# Instruction_Register.net
KiCad netlist of a schematic drawn in Altium Designer
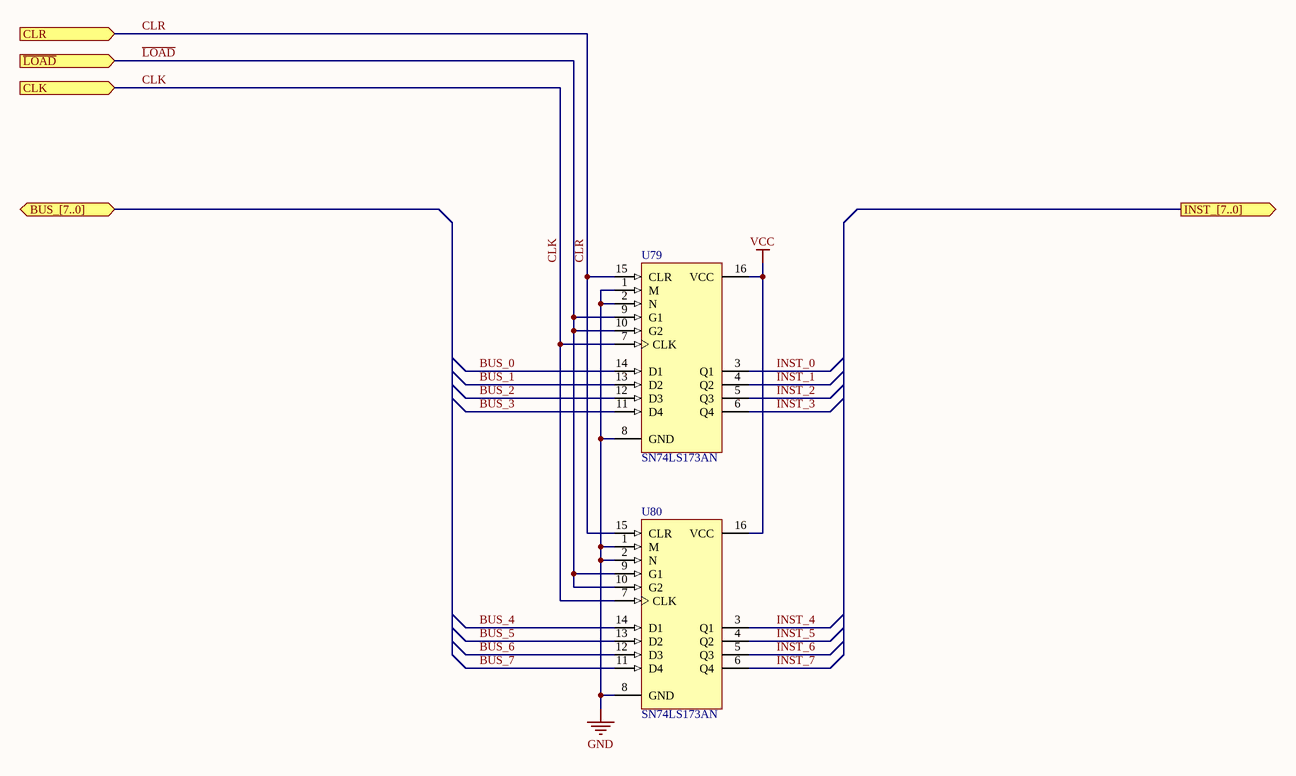
[diagram p0: Instruction Register.SchDoc]

(export (version "E")
  (design (tool "Eeschema 10.0.6"))
  (components
    (comp (ref "U79")
      (value "SN74LS173AN")
      (footprint "N016D")
      (description "4-Bit D-Type Register with 3-State Outputs")
      (fields (field (name "PUBLISHER") "Altium Limited"))
      (libsource (lib "TI Logic Flip-Flop") (part "SN74LS173AN"))
    )
    (comp (ref "U80")
      (value "SN74LS173AN")
      (footprint "N016D")
      (description "4-Bit D-Type Register with 3-State Outputs")
      (fields (field (name "PUBLISHER") "Altium Limited"))
      (libsource (lib "TI Logic Flip-Flop") (part "SN74LS173AN"))
    )
  )
  (nets
    (net (code "1") (name "/BUS_0") (class "Default")
      (node (ref "U79") (pin "14") (pinfunction "D1_14") (pintype "input"))
    )
    (net (code "2") (name "/BUS_1") (class "Default")
      (node (ref "U79") (pin "13") (pinfunction "D2_13") (pintype "input"))
    )
    (net (code "3") (name "/BUS_2") (class "Default")
      (node (ref "U79") (pin "12") (pinfunction "D3_12") (pintype "input"))
    )
    (net (code "4") (name "/BUS_3") (class "Default")
      (node (ref "U79") (pin "11") (pinfunction "D4_11") (pintype "input"))
    )
    (net (code "5") (name "/BUS_4") (class "Default")
      (node (ref "U80") (pin "14") (pinfunction "D1_14") (pintype "input"))
    )
    (net (code "6") (name "/BUS_5") (class "Default")
      (node (ref "U80") (pin "13") (pinfunction "D2_13") (pintype "input"))
    )
    (net (code "7") (name "/BUS_6") (class "Default")
      (node (ref "U80") (pin "12") (pinfunction "D3_12") (pintype "input"))
    )
    (net (code "8") (name "/BUS_7") (class "Default")
      (node (ref "U80") (pin "11") (pinfunction "D4_11") (pintype "input"))
    )
    (net (code "10") (name "/CLK") (class "Default")
      (node (ref "U79") (pin "7") (pinfunction "CLK_7") (pintype "input"))
      (node (ref "U80") (pin "7") (pinfunction "CLK_7") (pintype "input"))
    )
    (net (code "11") (name "/CLR") (class "Default")
      (node (ref "U79") (pin "15") (pinfunction "CLR_15") (pintype "input"))
      (node (ref "U80") (pin "15") (pinfunction "CLR_15") (pintype "input"))
    )
    (net (code "12") (name "/INST_0") (class "Default")
      (node (ref "U79") (pin "3") (pinfunction "Q1_3") (pintype "tri_state"))
    )
    (net (code "13") (name "/INST_1") (class "Default")
      (node (ref "U79") (pin "4") (pinfunction "Q2_4") (pintype "tri_state"))
    )
    (net (code "14") (name "/INST_2") (class "Default")
      (node (ref "U79") (pin "5") (pinfunction "Q3_5") (pintype "tri_state"))
    )
    (net (code "15") (name "/INST_3") (class "Default")
      (node (ref "U79") (pin "6") (pinfunction "Q4_6") (pintype "tri_state"))
    )
    (net (code "16") (name "/INST_4") (class "Default")
      (node (ref "U80") (pin "3") (pinfunction "Q1_3") (pintype "tri_state"))
    )
    (net (code "17") (name "/INST_5") (class "Default")
      (node (ref "U80") (pin "4") (pinfunction "Q2_4") (pintype "tri_state"))
    )
    (net (code "18") (name "/INST_6") (class "Default")
      (node (ref "U80") (pin "5") (pinfunction "Q3_5") (pintype "tri_state"))
    )
    (net (code "19") (name "/INST_7") (class "Default")
      (node (ref "U80") (pin "6") (pinfunction "Q4_6") (pintype "tri_state"))
    )
    (net (code "21") (name "/~{LOAD}") (class "Default")
      (node (ref "U79") (pin "10") (pinfunction "G2_10") (pintype "input"))
      (node (ref "U79") (pin "9") (pinfunction "G1_9") (pintype "input"))
      (node (ref "U80") (pin "10") (pinfunction "G2_10") (pintype "input"))
      (node (ref "U80") (pin "9") (pinfunction "G1_9") (pintype "input"))
    )
    (net (code "22") (name "GND") (class "Default")
      (node (ref "U79") (pin "1") (pinfunction "M_1") (pintype "input"))
      (node (ref "U79") (pin "2") (pinfunction "N_2") (pintype "input"))
      (node (ref "U79") (pin "8") (pinfunction "GND_8") (pintype "power_in"))
      (node (ref "U80") (pin "1") (pinfunction "M_1") (pintype "input"))
      (node (ref "U80") (pin "2") (pinfunction "N_2") (pintype "input"))
      (node (ref "U80") (pin "8") (pinfunction "GND_8") (pintype "power_in"))
    )
    (net (code "23") (name "VCC") (class "Default")
      (node (ref "U79") (pin "16") (pinfunction "VCC_16") (pintype "power_in"))
      (node (ref "U80") (pin "16") (pinfunction "VCC_16") (pintype "power_in"))
    )
  )
)
